# dimmer_v2.net
KiCad netlist of a schematic drawn in Altium Designer
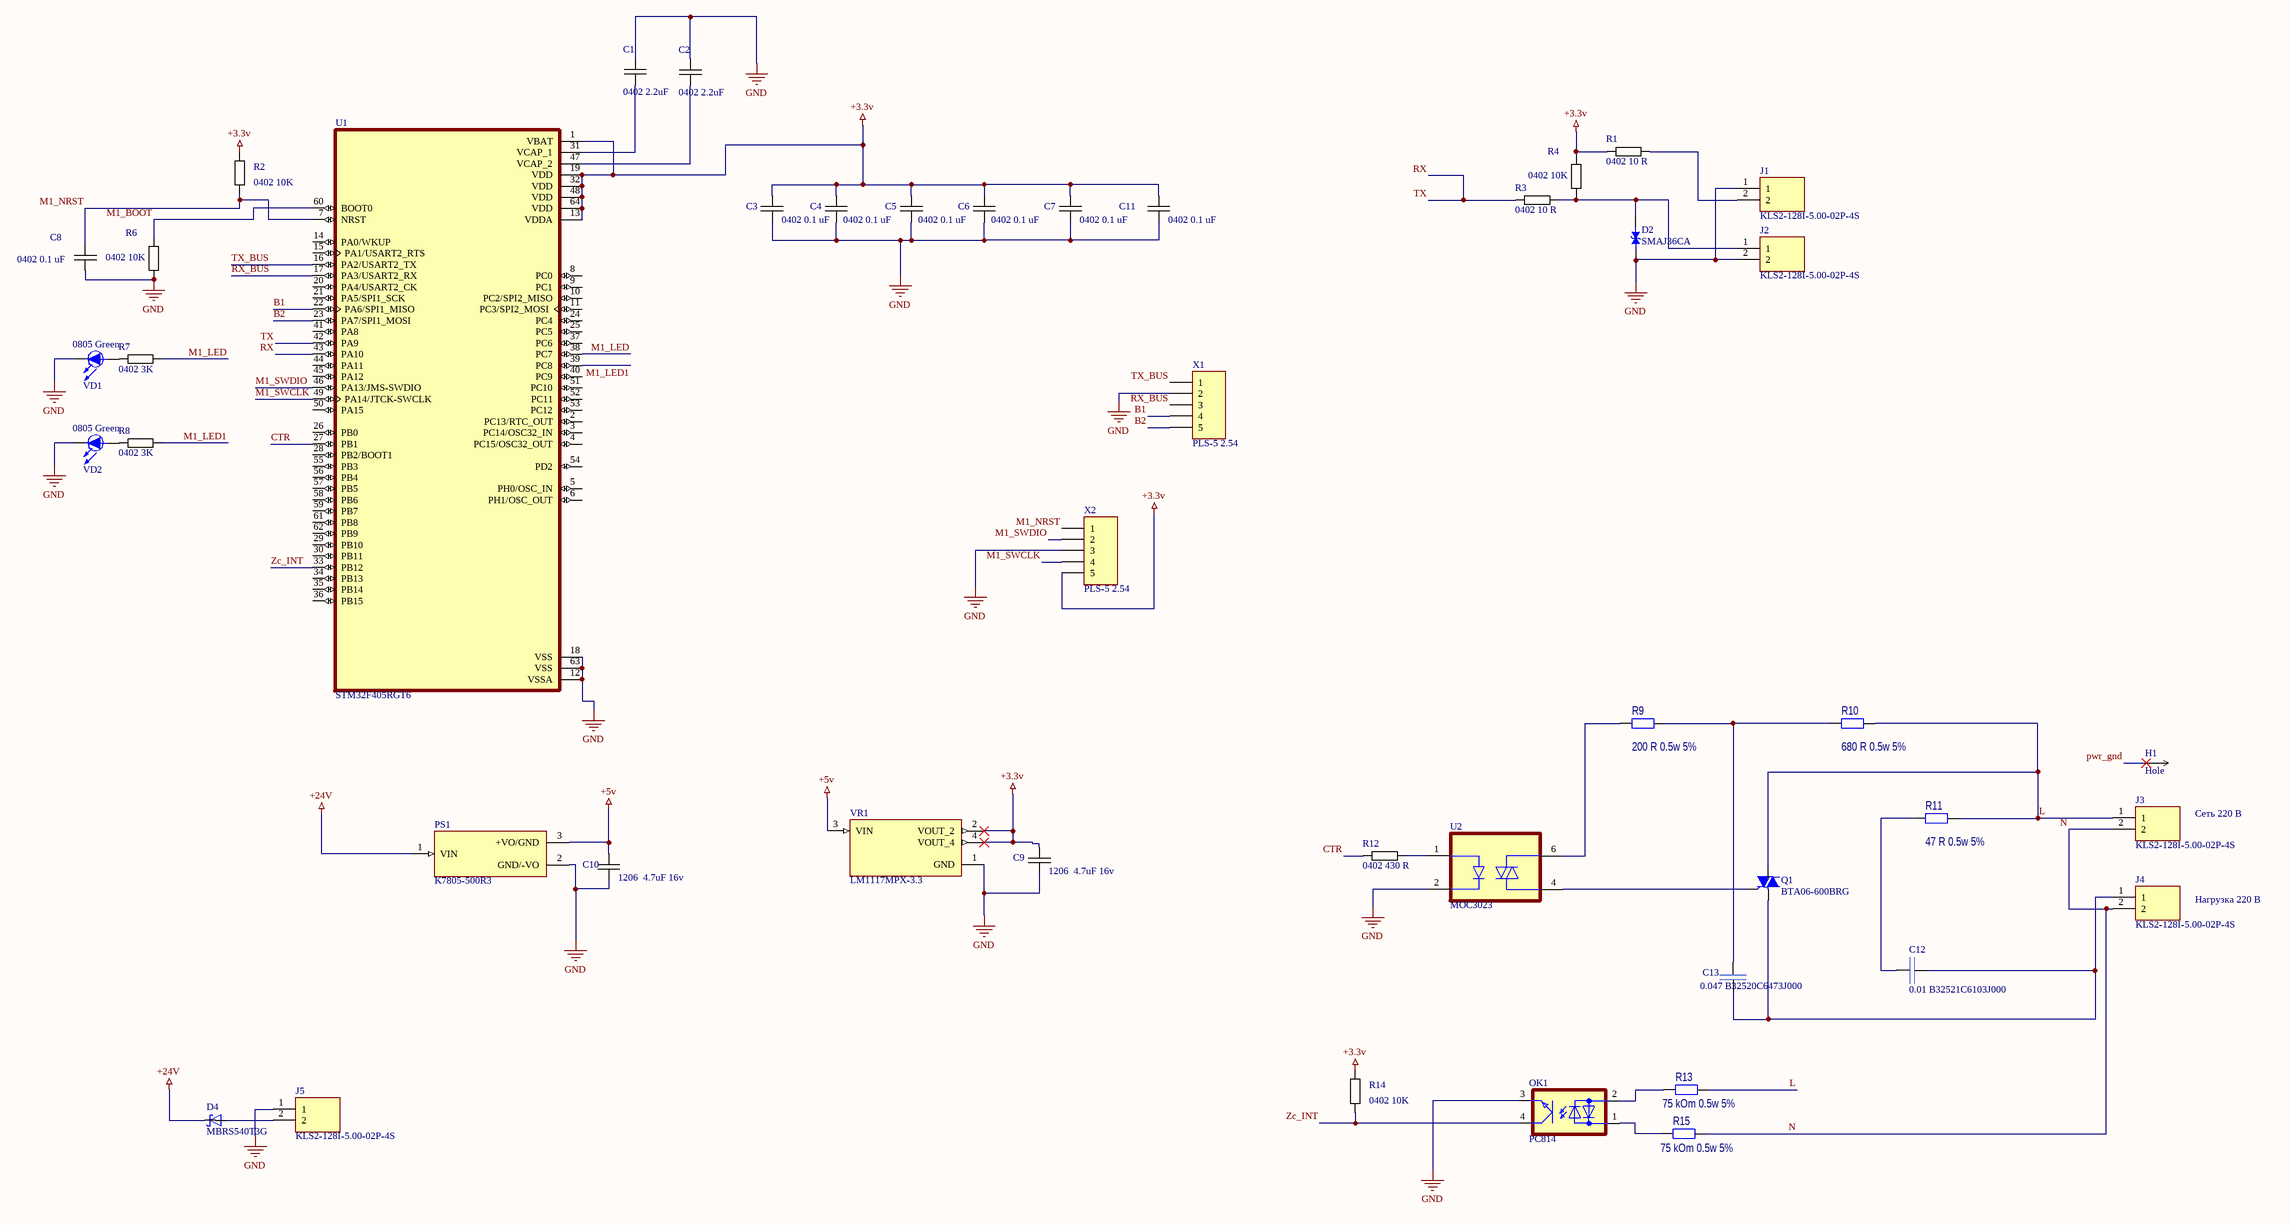
[diagram p0: dimmer_v2.SchDoc]

(export (version "E")
  (design (tool "Eeschema 10.0.6"))
  (components
    (comp (ref "C1")
      (value "0402 2.2uF")
      (footprint "CAPACITOR 0402")
      (description "Ceramic Capacitor SMD")
      (libsource (lib "Maks_lib") (part "Capasitor"))
    )
    (comp (ref "C2")
      (value "0402 2.2uF")
      (footprint "CAPACITOR 0402")
      (description "Ceramic Capacitor SMD")
      (libsource (lib "Maks_lib") (part "Capasitor"))
    )
    (comp (ref "C3")
      (value "0402 0.1 uF")
      (footprint "CAPACITOR 0402")
      (description "Ceramic Capacitor")
      (libsource (lib "Maks_lib") (part "Capasitor"))
    )
    (comp (ref "C4")
      (value "0402 0.1 uF")
      (footprint "CAPACITOR 0402")
      (description "Ceramic Capacitor")
      (libsource (lib "Maks_lib") (part "Capasitor"))
    )
    (comp (ref "C5")
      (value "0402 0.1 uF")
      (footprint "CAPACITOR 0402")
      (description "Ceramic Capacitor")
      (libsource (lib "Maks_lib") (part "Capasitor"))
    )
    (comp (ref "C6")
      (value "0402 0.1 uF")
      (footprint "CAPACITOR 0402")
      (description "Ceramic Capacitor")
      (libsource (lib "Maks_lib") (part "Capasitor"))
    )
    (comp (ref "C7")
      (value "0402 0.1 uF")
      (footprint "CAPACITOR 0402")
      (description "Ceramic Capacitor")
      (libsource (lib "Maks_lib") (part "Capasitor"))
    )
    (comp (ref "C8")
      (value "0402 0.1 uF")
      (footprint "CAPACITOR 0402")
      (description "Ceramic Capacitor")
      (libsource (lib "Maks_lib") (part "Capasitor"))
    )
    (comp (ref "C9")
      (value "1206  4.7uF 16v")
      (footprint "CAPACITOR 1206")
      (description "Ceramic Capacitor")
      (libsource (lib "Maks_lib") (part "Capasitor"))
    )
    (comp (ref "C10")
      (value "1206  4.7uF 16v")
      (footprint "CAPACITOR 1206")
      (description "Ceramic Capacitor")
      (libsource (lib "Maks_lib") (part "Capasitor"))
    )
    (comp (ref "C11")
      (value "0402 0.1 uF")
      (footprint "CAPACITOR 0402")
      (description "Ceramic Capacitor")
      (libsource (lib "Maks_lib") (part "Capasitor"))
    )
    (comp (ref "C12")
      (value "0.01 B32521C6103J000")
      (footprint "CAPRR1000W60L1300T400H900")
      (libsource (lib "HV_CAP") (part "HV_CAP"))
    )
    (comp (ref "C13")
      (value "0.047 B32520C6473J000")
      (footprint "CAPRR1000W60L1300T400H900")
      (libsource (lib "HV_CAP") (part "HV_CAP"))
    )
    (comp (ref "D2")
      (value "SMAJ36CA")
      (footprint "DIOM4325X250N")
      (libsource (lib "SMAJ36CA") (part "SMAJ36CA"))
    )
    (comp (ref "D4")
      (value "MBRS540T3G")
      (footprint "DIOM7958X213N")
      (description "Diode Schottky 40V 5A Surface Mount SMC")
      (fields (field (name "MF") "ON Semiconductor"))
      (libsource (lib "MBRS540T3G") (part "MBRS540T3G"))
    )
    (comp (ref "H1") (value "Hole") (footprint "Hole 1.5") (libsource (lib "Maks_lib") (part "Hole")))
    (comp (ref "J1")
      (value "KLS2-128I-5.00-02P-4S")
      (footprint "CUI_TB003-500-P02BE")
      (description "2~24 Poles, Screw Type, Horizontal, 5.0 Pitch, 26~14 _AWG_, Terminal Block Connector")
      (fields (field (name "MP") "TB003-500-P02BE") (field (name "MF") "CUI Devices"))
      (libsource (lib "TB003-500-P02BE") (part "TB003-500-P02BE"))
    )
    (comp (ref "J2")
      (value "KLS2-128I-5.00-02P-4S")
      (footprint "CUI_TB003-500-P02BE")
      (description "2~24 Poles, Screw Type, Horizontal, 5.0 Pitch, 26~14 _AWG_, Terminal Block Connector")
      (fields (field (name "MP") "TB003-500-P02BE") (field (name "MF") "CUI Devices"))
      (libsource (lib "TB003-500-P02BE") (part "TB003-500-P02BE"))
    )
    (comp (ref "J3")
      (value "KLS2-128I-5.00-02P-4S")
      (footprint "CUI_TB003-500-P02BE")
      (description "2~24 Poles, Screw Type, Horizontal, 5.0 Pitch, 26~14 _AWG_, Terminal Block Connector")
      (fields (field (name "MP") "TB003-500-P02BE") (field (name "MF") "CUI Devices"))
      (libsource (lib "TB003-500-P02BE") (part "TB003-500-P02BE"))
    )
    (comp (ref "J4")
      (value "KLS2-128I-5.00-02P-4S")
      (footprint "CUI_TB003-500-P02BE")
      (description "2~24 Poles, Screw Type, Horizontal, 5.0 Pitch, 26~14 _AWG_, Terminal Block Connector")
      (fields (field (name "MP") "TB003-500-P02BE") (field (name "MF") "CUI Devices"))
      (libsource (lib "TB003-500-P02BE") (part "TB003-500-P02BE"))
    )
    (comp (ref "J5")
      (value "KLS2-128I-5.00-02P-4S")
      (footprint "CUI_TB003-500-P02BE")
      (description "2~24 Poles, Screw Type, Horizontal, 5.0 Pitch, 26~14 _AWG_, Terminal Block Connector")
      (fields (field (name "MP") "TB003-500-P02BE") (field (name "MF") "CUI Devices"))
      (libsource (lib "TB003-500-P02BE") (part "TB003-500-P02BE"))
    )
    (comp (ref "OK1")
      (value "PC814")
      (footprint "DIL04")
      (description "#10-32 Round Head Machine Screw Slotted Drive Nylon")
      (fields (field (name "MF") "Essentra Components"))
      (libsource (lib "PC814") (part "PC814"))
    )
    (comp (ref "PS1")
      (value "K7805-500R3")
      (footprint "CONV_K7805-500R3")
      (fields (field (name "MF") "MORNSUN"))
      (libsource (lib "K7805-500R3") (part "K7805-500R3"))
    )
    (comp (ref "Q1")
      (value "BTA06-600BRG")
      (footprint "TO254P1040X460X1975-3")
      (description "TRIAC Standard 600V 6A Through Hole TO-220AB")
      (fields (field (name "MF") "STMicroelectronics"))
      (libsource (lib "BTA06-600BRG") (part "BTA06-600BRG"))
    )
    (comp (ref "R1")
      (value "0402 10 R")
      (footprint "Resistor 0402")
      (description "Resistor")
      (libsource (lib "Maks_lib") (part "Resistor"))
    )
    (comp (ref "R2")
      (value "0402 10K")
      (footprint "Resistor 0402")
      (description "Resistor")
      (libsource (lib "Maks_lib") (part "Resistor"))
    )
    (comp (ref "R3")
      (value "0402 10 R")
      (footprint "Resistor 0402")
      (description "Resistor")
      (libsource (lib "Maks_lib") (part "Resistor"))
    )
    (comp (ref "R4")
      (value "0402 10K")
      (footprint "Resistor 0402")
      (description "Resistor")
      (libsource (lib "Maks_lib") (part "Resistor"))
    )
    (comp (ref "R6")
      (value "0402 10K")
      (footprint "Resistor 0402")
      (description "Resistor")
      (libsource (lib "Maks_lib") (part "Resistor"))
    )
    (comp (ref "R7")
      (value "0402 3K")
      (footprint "Resistor 0402")
      (description "Resistor")
      (libsource (lib "Maks_lib") (part "Resistor"))
    )
    (comp (ref "R8")
      (value "0402 3K")
      (footprint "Resistor 0402")
      (description "Resistor")
      (libsource (lib "Maks_lib") (part "Resistor"))
    )
    (comp (ref "R9")
      (value "200 R 0.5w 5%")
      (footprint "MF-200 V")
      (description "Резистор")
      (libsource (lib "RCL") (part "Res"))
    )
    (comp (ref "R10")
      (value "680 R 0.5w 5%")
      (footprint "MF-200 V")
      (description "Резистор")
      (libsource (lib "RCL") (part "Res"))
    )
    (comp (ref "R11")
      (value "47 R 0.5w 5%")
      (footprint "MF-200 V")
      (description "Резистор")
      (libsource (lib "RCL") (part "Res"))
    )
    (comp (ref "R12")
      (value "0402 430 R")
      (footprint "Resistor 0402")
      (description "Resistor")
      (libsource (lib "Maks_lib") (part "Resistor"))
    )
    (comp (ref "R13")
      (value "75 kOm 0.5w 5%")
      (footprint "MF-200 V")
      (description "Резистор")
      (libsource (lib "RCL") (part "Res"))
    )
    (comp (ref "R14")
      (value "0402 10K")
      (footprint "Resistor 0402")
      (description "Resistor")
      (libsource (lib "Maks_lib") (part "Resistor"))
    )
    (comp (ref "R15")
      (value "75 kOm 0.5w 5%")
      (footprint "MF-200 V")
      (description "Резистор")
      (libsource (lib "RCL") (part "Res"))
    )
    (comp (ref "U1")
      (value "STM32F405RGT6")
      (footprint "QFP50P1200X1200X160-64N")
      (libsource (lib "STM32F405RGT6") (part "STM32F405RGT6"))
    )
    (comp (ref "U2")
      (value "MOC3023")
      (footprint "DIP762W48P254L889H508Q6")
      (description "Optoisolator Triac Output 5300Vrms 1 Channel 6-DIP")
      (fields (field (name "MF") "ON Semiconductor"))
      (libsource (lib "MOC3023") (part "MOC3023"))
    )
    (comp (ref "VD1")
      (value "0805 Green")
      (footprint "0805-")
      (description "Green")
      (libsource (lib "DT") (part "LED SMD"))
    )
    (comp (ref "VD2")
      (value "0805 Green")
      (footprint "0805-")
      (description "Green")
      (libsource (lib "DT") (part "LED SMD"))
    )
    (comp (ref "VR1")
      (value "LM1117MPX-3.3")
      (footprint "VREG_LM1117MPX-3.3")
      (description "800-mA 3.3-V linear voltage regulator")
      (fields (field (name "MF") "Texas Instruments"))
      (libsource (lib "LM1117MPX-3.3") (part "LM1117MPX-3.3"))
    )
    (comp (ref "X1")
      (value "PLS-5 2.54")
      (footprint "PLS-5-3D")
      (description "Header, 5-Pin")
      (fields (field (name "PARTNUMBER") "PLS-5"))
      (libsource (lib "AX_Altium_v2.3") (part "PLS-5"))
    )
    (comp (ref "X2")
      (value "PLS-5 2.54")
      (footprint "PLS-5-3D")
      (description "Header, 5-Pin")
      (fields (field (name "PARTNUMBER") "PLS-5"))
      (libsource (lib "AX_Altium_v2.3") (part "PLS-5"))
    )
  )
  (nets
    (net (code "1") (name "+3.3v") (class "Default")
      (node (ref "C11") (pin "1") (pinfunction "1_1") (pintype "passive"))
      (node (ref "C3") (pin "1") (pinfunction "1_1") (pintype "passive"))
      (node (ref "C4") (pin "1") (pinfunction "1_1") (pintype "passive"))
      (node (ref "C5") (pin "1") (pinfunction "1_1") (pintype "passive"))
      (node (ref "C6") (pin "1") (pinfunction "1_1") (pintype "passive"))
      (node (ref "C7") (pin "1") (pinfunction "1_1") (pintype "passive"))
      (node (ref "C9") (pin "1") (pinfunction "1_1") (pintype "passive"))
      (node (ref "R1") (pin "2") (pinfunction "2_2") (pintype "passive"))
      (node (ref "R14") (pin "2") (pinfunction "2_2") (pintype "passive"))
      (node (ref "R2") (pin "2") (pinfunction "2_2") (pintype "passive"))
      (node (ref "R4") (pin "1") (pinfunction "1_1") (pintype "passive"))
      (node (ref "U1") (pin "1") (pinfunction "VBAT_1") (pintype "power_in"))
      (node (ref "U1") (pin "13") (pinfunction "VDDA_13") (pintype "power_in"))
      (node (ref "U1") (pin "19") (pinfunction "VDD_19") (pintype "power_in"))
      (node (ref "U1") (pin "32") (pinfunction "VDD_32") (pintype "power_in"))
      (node (ref "U1") (pin "48") (pinfunction "VDD_48") (pintype "power_in"))
      (node (ref "U1") (pin "64") (pinfunction "VDD_64") (pintype "power_in"))
      (node (ref "VR1") (pin "2") (pinfunction "VOUT_2_2") (pintype "output"))
      (node (ref "VR1") (pin "4") (pinfunction "VOUT_4_4") (pintype "output"))
      (node (ref "X2") (pin "5") (pinfunction "5_5") (pintype "passive"))
    )
    (net (code "2") (name "+5v") (class "Default")
      (node (ref "C10") (pin "1") (pinfunction "1_1") (pintype "passive"))
      (node (ref "PS1") (pin "3") (pinfunction "+VO/GND_3") (pintype "passive"))
      (node (ref "VR1") (pin "3") (pinfunction "VIN_3") (pintype "input"))
    )
    (net (code "3") (name "+24V") (class "Default")
      (node (ref "D4") (pin "C") (pinfunction "C_C") (pintype "passive"))
      (node (ref "PS1") (pin "1") (pinfunction "VIN_1") (pintype "input"))
    )
    (net (code "4") (name "/B1") (class "Default")
      (node (ref "U1") (pin "22") (pinfunction "PA6/SPI1_MISO_22") (pintype "bidirectional"))
      (node (ref "X1") (pin "4") (pinfunction "4_4") (pintype "passive"))
    )
    (net (code "5") (name "/B2") (class "Default")
      (node (ref "U1") (pin "23") (pinfunction "PA7/SPI1_MOSI_23") (pintype "bidirectional"))
      (node (ref "X1") (pin "5") (pinfunction "5_5") (pintype "passive"))
    )
    (net (code "6") (name "/CTR") (class "Default")
      (node (ref "R12") (pin "2") (pinfunction "2_2") (pintype "passive"))
      (node (ref "U1") (pin "27") (pinfunction "PB1_27") (pintype "bidirectional"))
    )
    (net (code "7") (name "/L") (class "Default")
      (node (ref "J3") (pin "1") (pinfunction "1_1") (pintype "passive"))
      (node (ref "Q1") (pin "2") (pinfunction "A2_2") (pintype "passive"))
      (node (ref "R10") (pin "2") (pinfunction "2_2") (pintype "passive"))
      (node (ref "R11") (pin "2") (pinfunction "2_2") (pintype "passive"))
      (node (ref "R13") (pin "2") (pinfunction "2_2") (pintype "passive"))
    )
    (net (code "8") (name "/M1_BOOT") (class "Default")
      (node (ref "R6") (pin "1") (pinfunction "1_1") (pintype "passive"))
      (node (ref "U1") (pin "60") (pinfunction "BOOT0_60") (pintype "bidirectional"))
    )
    (net (code "9") (name "/M1_LED") (class "Default")
      (node (ref "R7") (pin "1") (pinfunction "1_1") (pintype "passive"))
      (node (ref "U1") (pin "38") (pinfunction "PC7_38") (pintype "bidirectional"))
    )
    (net (code "10") (name "/M1_LED1") (class "Default")
      (node (ref "R8") (pin "1") (pinfunction "1_1") (pintype "passive"))
      (node (ref "U1") (pin "39") (pinfunction "PC8_39") (pintype "bidirectional"))
    )
    (net (code "11") (name "/M1_NRST") (class "Default")
      (node (ref "C8") (pin "2") (pinfunction "2_2") (pintype "passive"))
      (node (ref "R2") (pin "1") (pinfunction "1_1") (pintype "passive"))
      (node (ref "U1") (pin "7") (pinfunction "NRST_7") (pintype "bidirectional"))
      (node (ref "X2") (pin "1") (pinfunction "1_1") (pintype "passive"))
    )
    (net (code "12") (name "/M1_SWCLK") (class "Default")
      (node (ref "U1") (pin "49") (pinfunction "PA14/JTCK-SWCLK_49") (pintype "bidirectional"))
      (node (ref "X2") (pin "4") (pinfunction "4_4") (pintype "passive"))
    )
    (net (code "13") (name "/M1_SWDIO") (class "Default")
      (node (ref "U1") (pin "46") (pinfunction "PA13/JMS-SWDIO_46") (pintype "bidirectional"))
      (node (ref "X2") (pin "2") (pinfunction "2_2") (pintype "passive"))
    )
    (net (code "14") (name "/N") (class "Default")
      (node (ref "J3") (pin "2") (pinfunction "2_2") (pintype "passive"))
      (node (ref "J4") (pin "2") (pinfunction "2_2") (pintype "passive"))
      (node (ref "R15") (pin "2") (pinfunction "2_2") (pintype "passive"))
    )
    (net (code "15") (name "/RX") (class "Default")
      (node (ref "R3") (pin "2") (pinfunction "2_2") (pintype "passive"))
      (node (ref "U1") (pin "42") (pinfunction "PA9_42") (pintype "bidirectional"))
      (node (ref "U1") (pin "43") (pinfunction "PA10_43") (pintype "bidirectional"))
    )
    (net (code "16") (name "/RX_BUS") (class "Default")
      (node (ref "U1") (pin "17") (pinfunction "PA3/USART2_RX_17") (pintype "bidirectional"))
      (node (ref "X1") (pin "3") (pinfunction "3_3") (pintype "passive"))
    )
    (net (code "17") (name "/TX_BUS") (class "Default")
      (node (ref "U1") (pin "16") (pinfunction "PA2/USART2_TX_16") (pintype "bidirectional"))
      (node (ref "X1") (pin "1") (pinfunction "1_1") (pintype "passive"))
    )
    (net (code "18") (name "/Zc_INT") (class "Default")
      (node (ref "OK1") (pin "4") (pinfunction "C_4") (pintype "passive"))
      (node (ref "R14") (pin "1") (pinfunction "1_1") (pintype "passive"))
      (node (ref "U1") (pin "33") (pinfunction "PB12_33") (pintype "bidirectional"))
    )
    (net (code "19") (name "/pwr_gnd") (class "Default")
      (node (ref "H1") (pin "0") (pinfunction "0_0") (pintype "passive+no_connect"))
    )
    (net (code "20") (name "GND") (class "Default")
      (node (ref "C1") (pin "1") (pinfunction "1_1") (pintype "passive"))
      (node (ref "C10") (pin "2") (pinfunction "2_2") (pintype "passive"))
      (node (ref "C11") (pin "2") (pinfunction "2_2") (pintype "passive"))
      (node (ref "C2") (pin "1") (pinfunction "1_1") (pintype "passive"))
      (node (ref "C3") (pin "2") (pinfunction "2_2") (pintype "passive"))
      (node (ref "C4") (pin "2") (pinfunction "2_2") (pintype "passive"))
      (node (ref "C5") (pin "2") (pinfunction "2_2") (pintype "passive"))
      (node (ref "C6") (pin "2") (pinfunction "2_2") (pintype "passive"))
      (node (ref "C7") (pin "2") (pinfunction "2_2") (pintype "passive"))
      (node (ref "C8") (pin "1") (pinfunction "1_1") (pintype "passive"))
      (node (ref "C9") (pin "2") (pinfunction "2_2") (pintype "passive"))
      (node (ref "D2") (pin "2") (pinfunction "2_2") (pintype "passive"))
      (node (ref "J1") (pin "1") (pinfunction "1_1") (pintype "passive"))
      (node (ref "J2") (pin "2") (pinfunction "2_2") (pintype "passive"))
      (node (ref "J5") (pin "1") (pinfunction "1_1") (pintype "passive"))
      (node (ref "OK1") (pin "3") (pinfunction "E_3") (pintype "passive"))
      (node (ref "PS1") (pin "2") (pinfunction "GND/-VO_2") (pintype "passive"))
      (node (ref "R6") (pin "2") (pinfunction "2_2") (pintype "passive"))
      (node (ref "U1") (pin "12") (pinfunction "VSSA_12") (pintype "power_in"))
      (node (ref "U1") (pin "18") (pinfunction "VSS_18") (pintype "power_in"))
      (node (ref "U1") (pin "63") (pinfunction "VSS_63") (pintype "power_in"))
      (node (ref "U2") (pin "2") (pinfunction "CATHODE_2") (pintype "passive"))
      (node (ref "VD1") (pin "K") (pinfunction "k_K") (pintype "passive"))
      (node (ref "VD2") (pin "K") (pinfunction "k_K") (pintype "passive"))
      (node (ref "VR1") (pin "1") (pinfunction "GND_1") (pintype "power_in"))
      (node (ref "X1") (pin "2") (pinfunction "2_2") (pintype "passive"))
      (node (ref "X2") (pin "3") (pinfunction "3_3") (pintype "passive"))
    )
    (net (code "21") (name "Net-(C12-Pad2)") (class "Default")
      (node (ref "C12") (pin "2") (pinfunction "2_2") (pintype "passive"))
      (node (ref "R11") (pin "1") (pinfunction "1_1") (pintype "passive"))
    )
    (net (code "22") (name "Net-(C13-Pad1)") (class "Default")
      (node (ref "C13") (pin "1") (pinfunction "1_1") (pintype "passive"))
      (node (ref "R10") (pin "1") (pinfunction "1_1") (pintype "passive"))
      (node (ref "R9") (pin "2") (pinfunction "2_2") (pintype "passive"))
    )
    (net (code "23") (name "Net-(D2-Pad1)") (class "Default")
      (node (ref "D2") (pin "1") (pinfunction "1_1") (pintype "passive"))
      (node (ref "J2") (pin "1") (pinfunction "1_1") (pintype "passive"))
      (node (ref "R3") (pin "1") (pinfunction "1_1") (pintype "passive"))
      (node (ref "R4") (pin "2") (pinfunction "2_2") (pintype "passive"))
    )
    (net (code "24") (name "Net-(D4-PadA)") (class "Default")
      (node (ref "D4") (pin "A") (pinfunction "A_A") (pintype "passive"))
      (node (ref "J5") (pin "2") (pinfunction "2_2") (pintype "passive"))
    )
    (net (code "25") (name "Net-(J1-Pad2)") (class "Default")
      (node (ref "J1") (pin "2") (pinfunction "2_2") (pintype "passive"))
      (node (ref "R1") (pin "1") (pinfunction "1_1") (pintype "passive"))
    )
    (net (code "26") (name "Net-(OK1-AC1)") (class "Default")
      (node (ref "OK1") (pin "1") (pinfunction "AC1_1") (pintype "passive"))
      (node (ref "R15") (pin "1") (pinfunction "1_1") (pintype "passive"))
    )
    (net (code "27") (name "Net-(OK1-AC2)") (class "Default")
      (node (ref "OK1") (pin "2") (pinfunction "AC2_2") (pintype "passive"))
      (node (ref "R13") (pin "1") (pinfunction "1_1") (pintype "passive"))
    )
    (net (code "28") (name "Net-(Q1-A1)") (class "Default")
      (node (ref "C12") (pin "1") (pinfunction "1_1") (pintype "passive"))
      (node (ref "C13") (pin "2") (pinfunction "2_2") (pintype "passive"))
      (node (ref "J4") (pin "1") (pinfunction "1_1") (pintype "passive"))
      (node (ref "Q1") (pin "1") (pinfunction "A1_1") (pintype "passive"))
    )
    (net (code "29") (name "Net-(Q1-G)") (class "Default")
      (node (ref "Q1") (pin "3") (pinfunction "G_3") (pintype "passive"))
      (node (ref "U2") (pin "4") (pinfunction "MAINTERMINAL_1_4") (pintype "passive"))
    )
    (net (code "30") (name "Net-(U1-VCAP_1)") (class "Default")
      (node (ref "C1") (pin "2") (pinfunction "2_2") (pintype "passive"))
      (node (ref "U1") (pin "31") (pinfunction "VCAP_1_31") (pintype "power_in"))
    )
    (net (code "31") (name "Net-(U1-VCAP_2)") (class "Default")
      (node (ref "C2") (pin "2") (pinfunction "2_2") (pintype "passive"))
      (node (ref "U1") (pin "47") (pinfunction "VCAP_2_47") (pintype "power_in"))
    )
    (net (code "32") (name "Net-(U2-ANODE)") (class "Default")
      (node (ref "R12") (pin "1") (pinfunction "1_1") (pintype "passive"))
      (node (ref "U2") (pin "1") (pinfunction "ANODE_1") (pintype "passive"))
    )
    (net (code "33") (name "Net-(U2-MAINTERMINAL_2)") (class "Default")
      (node (ref "R9") (pin "1") (pinfunction "1_1") (pintype "passive"))
      (node (ref "U2") (pin "6") (pinfunction "MAINTERMINAL_2_6") (pintype "passive"))
    )
    (net (code "34") (name "Net-(VD1-a)") (class "Default")
      (node (ref "R7") (pin "2") (pinfunction "2_2") (pintype "passive"))
      (node (ref "VD1") (pin "A") (pinfunction "a_A") (pintype "passive"))
    )
    (net (code "35") (name "Net-(VD2-a)") (class "Default")
      (node (ref "R8") (pin "2") (pinfunction "2_2") (pintype "passive"))
      (node (ref "VD2") (pin "A") (pinfunction "a_A") (pintype "passive"))
    )
    (net (code "36") (name "unconnected-(U1-PA0{slash}WKUP-Pad14)") (class "Default")
      (node (ref "U1") (pin "14") (pinfunction "PA0/WKUP_14") (pintype "bidirectional"))
    )
    (net (code "37") (name "unconnected-(U1-PA1{slash}USART2_RTS-Pad15)") (class "Default")
      (node (ref "U1") (pin "15") (pinfunction "PA1/USART2_RTS_15") (pintype "bidirectional"))
    )
    (net (code "38") (name "unconnected-(U1-PA4{slash}USART2_CK-Pad20)") (class "Default")
      (node (ref "U1") (pin "20") (pinfunction "PA4/USART2_CK_20") (pintype "bidirectional"))
    )
    (net (code "39") (name "unconnected-(U1-PA5{slash}SPI1_SCK-Pad21)") (class "Default")
      (node (ref "U1") (pin "21") (pinfunction "PA5/SPI1_SCK_21") (pintype "bidirectional"))
    )
    (net (code "40") (name "unconnected-(U1-PA8-Pad41)") (class "Default")
      (node (ref "U1") (pin "41") (pinfunction "PA8_41") (pintype "bidirectional"))
    )
    (net (code "41") (name "unconnected-(U1-PA11-Pad44)") (class "Default")
      (node (ref "U1") (pin "44") (pinfunction "PA11_44") (pintype "bidirectional"))
    )
    (net (code "42") (name "unconnected-(U1-PA12-Pad45)") (class "Default")
      (node (ref "U1") (pin "45") (pinfunction "PA12_45") (pintype "bidirectional"))
    )
    (net (code "43") (name "unconnected-(U1-PA15-Pad50)") (class "Default")
      (node (ref "U1") (pin "50") (pinfunction "PA15_50") (pintype "bidirectional"))
    )
    (net (code "44") (name "unconnected-(U1-PB0-Pad26)") (class "Default")
      (node (ref "U1") (pin "26") (pinfunction "PB0_26") (pintype "bidirectional"))
    )
    (net (code "45") (name "unconnected-(U1-PB2{slash}BOOT1-Pad28)") (class "Default")
      (node (ref "U1") (pin "28") (pinfunction "PB2/BOOT1_28") (pintype "bidirectional"))
    )
    (net (code "46") (name "unconnected-(U1-PB3-Pad55)") (class "Default")
      (node (ref "U1") (pin "55") (pinfunction "PB3_55") (pintype "bidirectional"))
    )
    (net (code "47") (name "unconnected-(U1-PB4-Pad56)") (class "Default")
      (node (ref "U1") (pin "56") (pinfunction "PB4_56") (pintype "bidirectional"))
    )
    (net (code "48") (name "unconnected-(U1-PB5-Pad57)") (class "Default")
      (node (ref "U1") (pin "57") (pinfunction "PB5_57") (pintype "bidirectional"))
    )
    (net (code "49") (name "unconnected-(U1-PB6-Pad58)") (class "Default")
      (node (ref "U1") (pin "58") (pinfunction "PB6_58") (pintype "bidirectional"))
    )
    (net (code "50") (name "unconnected-(U1-PB7-Pad59)") (class "Default")
      (node (ref "U1") (pin "59") (pinfunction "PB7_59") (pintype "bidirectional"))
    )
    (net (code "51") (name "unconnected-(U1-PB8-Pad61)") (class "Default")
      (node (ref "U1") (pin "61") (pinfunction "PB8_61") (pintype "bidirectional"))
    )
    (net (code "52") (name "unconnected-(U1-PB9-Pad62)") (class "Default")
      (node (ref "U1") (pin "62") (pinfunction "PB9_62") (pintype "bidirectional"))
    )
    (net (code "53") (name "unconnected-(U1-PB10-Pad29)") (class "Default")
      (node (ref "U1") (pin "29") (pinfunction "PB10_29") (pintype "bidirectional"))
    )
    (net (code "54") (name "unconnected-(U1-PB11-Pad30)") (class "Default")
      (node (ref "U1") (pin "30") (pinfunction "PB11_30") (pintype "bidirectional"))
    )
    (net (code "55") (name "unconnected-(U1-PB13-Pad34)") (class "Default")
      (node (ref "U1") (pin "34") (pinfunction "PB13_34") (pintype "bidirectional"))
    )
    (net (code "56") (name "unconnected-(U1-PB14-Pad35)") (class "Default")
      (node (ref "U1") (pin "35") (pinfunction "PB14_35") (pintype "bidirectional"))
    )
    (net (code "57") (name "unconnected-(U1-PB15-Pad36)") (class "Default")
      (node (ref "U1") (pin "36") (pinfunction "PB15_36") (pintype "bidirectional"))
    )
    (net (code "58") (name "unconnected-(U1-PC0-Pad8)") (class "Default")
      (node (ref "U1") (pin "8") (pinfunction "PC0_8") (pintype "bidirectional"))
    )
    (net (code "59") (name "unconnected-(U1-PC1-Pad9)") (class "Default")
      (node (ref "U1") (pin "9") (pinfunction "PC1_9") (pintype "bidirectional"))
    )
    (net (code "60") (name "unconnected-(U1-PC2{slash}SPI2_MISO-Pad10)") (class "Default")
      (node (ref "U1") (pin "10") (pinfunction "PC2/SPI2_MISO_10") (pintype "bidirectional"))
    )
    (net (code "61") (name "unconnected-(U1-PC3{slash}SPI2_MOSI-Pad11)") (class "Default")
      (node (ref "U1") (pin "11") (pinfunction "PC3/SPI2_MOSI_11") (pintype "bidirectional"))
    )
    (net (code "62") (name "unconnected-(U1-PC4-Pad24)") (class "Default")
      (node (ref "U1") (pin "24") (pinfunction "PC4_24") (pintype "bidirectional"))
    )
    (net (code "63") (name "unconnected-(U1-PC5-Pad25)") (class "Default")
      (node (ref "U1") (pin "25") (pinfunction "PC5_25") (pintype "bidirectional"))
    )
    (net (code "64") (name "unconnected-(U1-PC6-Pad37)") (class "Default")
      (node (ref "U1") (pin "37") (pinfunction "PC6_37") (pintype "bidirectional"))
    )
    (net (code "65") (name "unconnected-(U1-PC9-Pad40)") (class "Default")
      (node (ref "U1") (pin "40") (pinfunction "PC9_40") (pintype "bidirectional"))
    )
    (net (code "66") (name "unconnected-(U1-PC10-Pad51)") (class "Default")
      (node (ref "U1") (pin "51") (pinfunction "PC10_51") (pintype "bidirectional"))
    )
    (net (code "67") (name "unconnected-(U1-PC11-Pad52)") (class "Default")
      (node (ref "U1") (pin "52") (pinfunction "PC11_52") (pintype "bidirectional"))
    )
    (net (code "68") (name "unconnected-(U1-PC12-Pad53)") (class "Default")
      (node (ref "U1") (pin "53") (pinfunction "PC12_53") (pintype "bidirectional"))
    )
    (net (code "69") (name "unconnected-(U1-PC13{slash}RTC_OUT-Pad2)") (class "Default")
      (node (ref "U1") (pin "2") (pinfunction "PC13/RTC_OUT_2") (pintype "bidirectional"))
    )
    (net (code "70") (name "unconnected-(U1-PC14{slash}OSC32_IN-Pad3)") (class "Default")
      (node (ref "U1") (pin "3") (pinfunction "PC14/OSC32_IN_3") (pintype "bidirectional"))
    )
    (net (code "71") (name "unconnected-(U1-PC15{slash}OSC32_OUT-Pad4)") (class "Default")
      (node (ref "U1") (pin "4") (pinfunction "PC15/OSC32_OUT_4") (pintype "bidirectional"))
    )
    (net (code "72") (name "unconnected-(U1-PD2-Pad54)") (class "Default")
      (node (ref "U1") (pin "54") (pinfunction "PD2_54") (pintype "bidirectional"))
    )
    (net (code "73") (name "unconnected-(U1-PH0{slash}OSC_IN-Pad5)") (class "Default")
      (node (ref "U1") (pin "5") (pinfunction "PH0/OSC_IN_5") (pintype "bidirectional"))
    )
    (net (code "74") (name "unconnected-(U1-PH1{slash}OSC_OUT-Pad6)") (class "Default")
      (node (ref "U1") (pin "6") (pinfunction "PH1/OSC_OUT_6") (pintype "bidirectional"))
    )
  )
)
